# c2020_schematic.net
KiCad netlist of a schematic drawn in Altium Designer
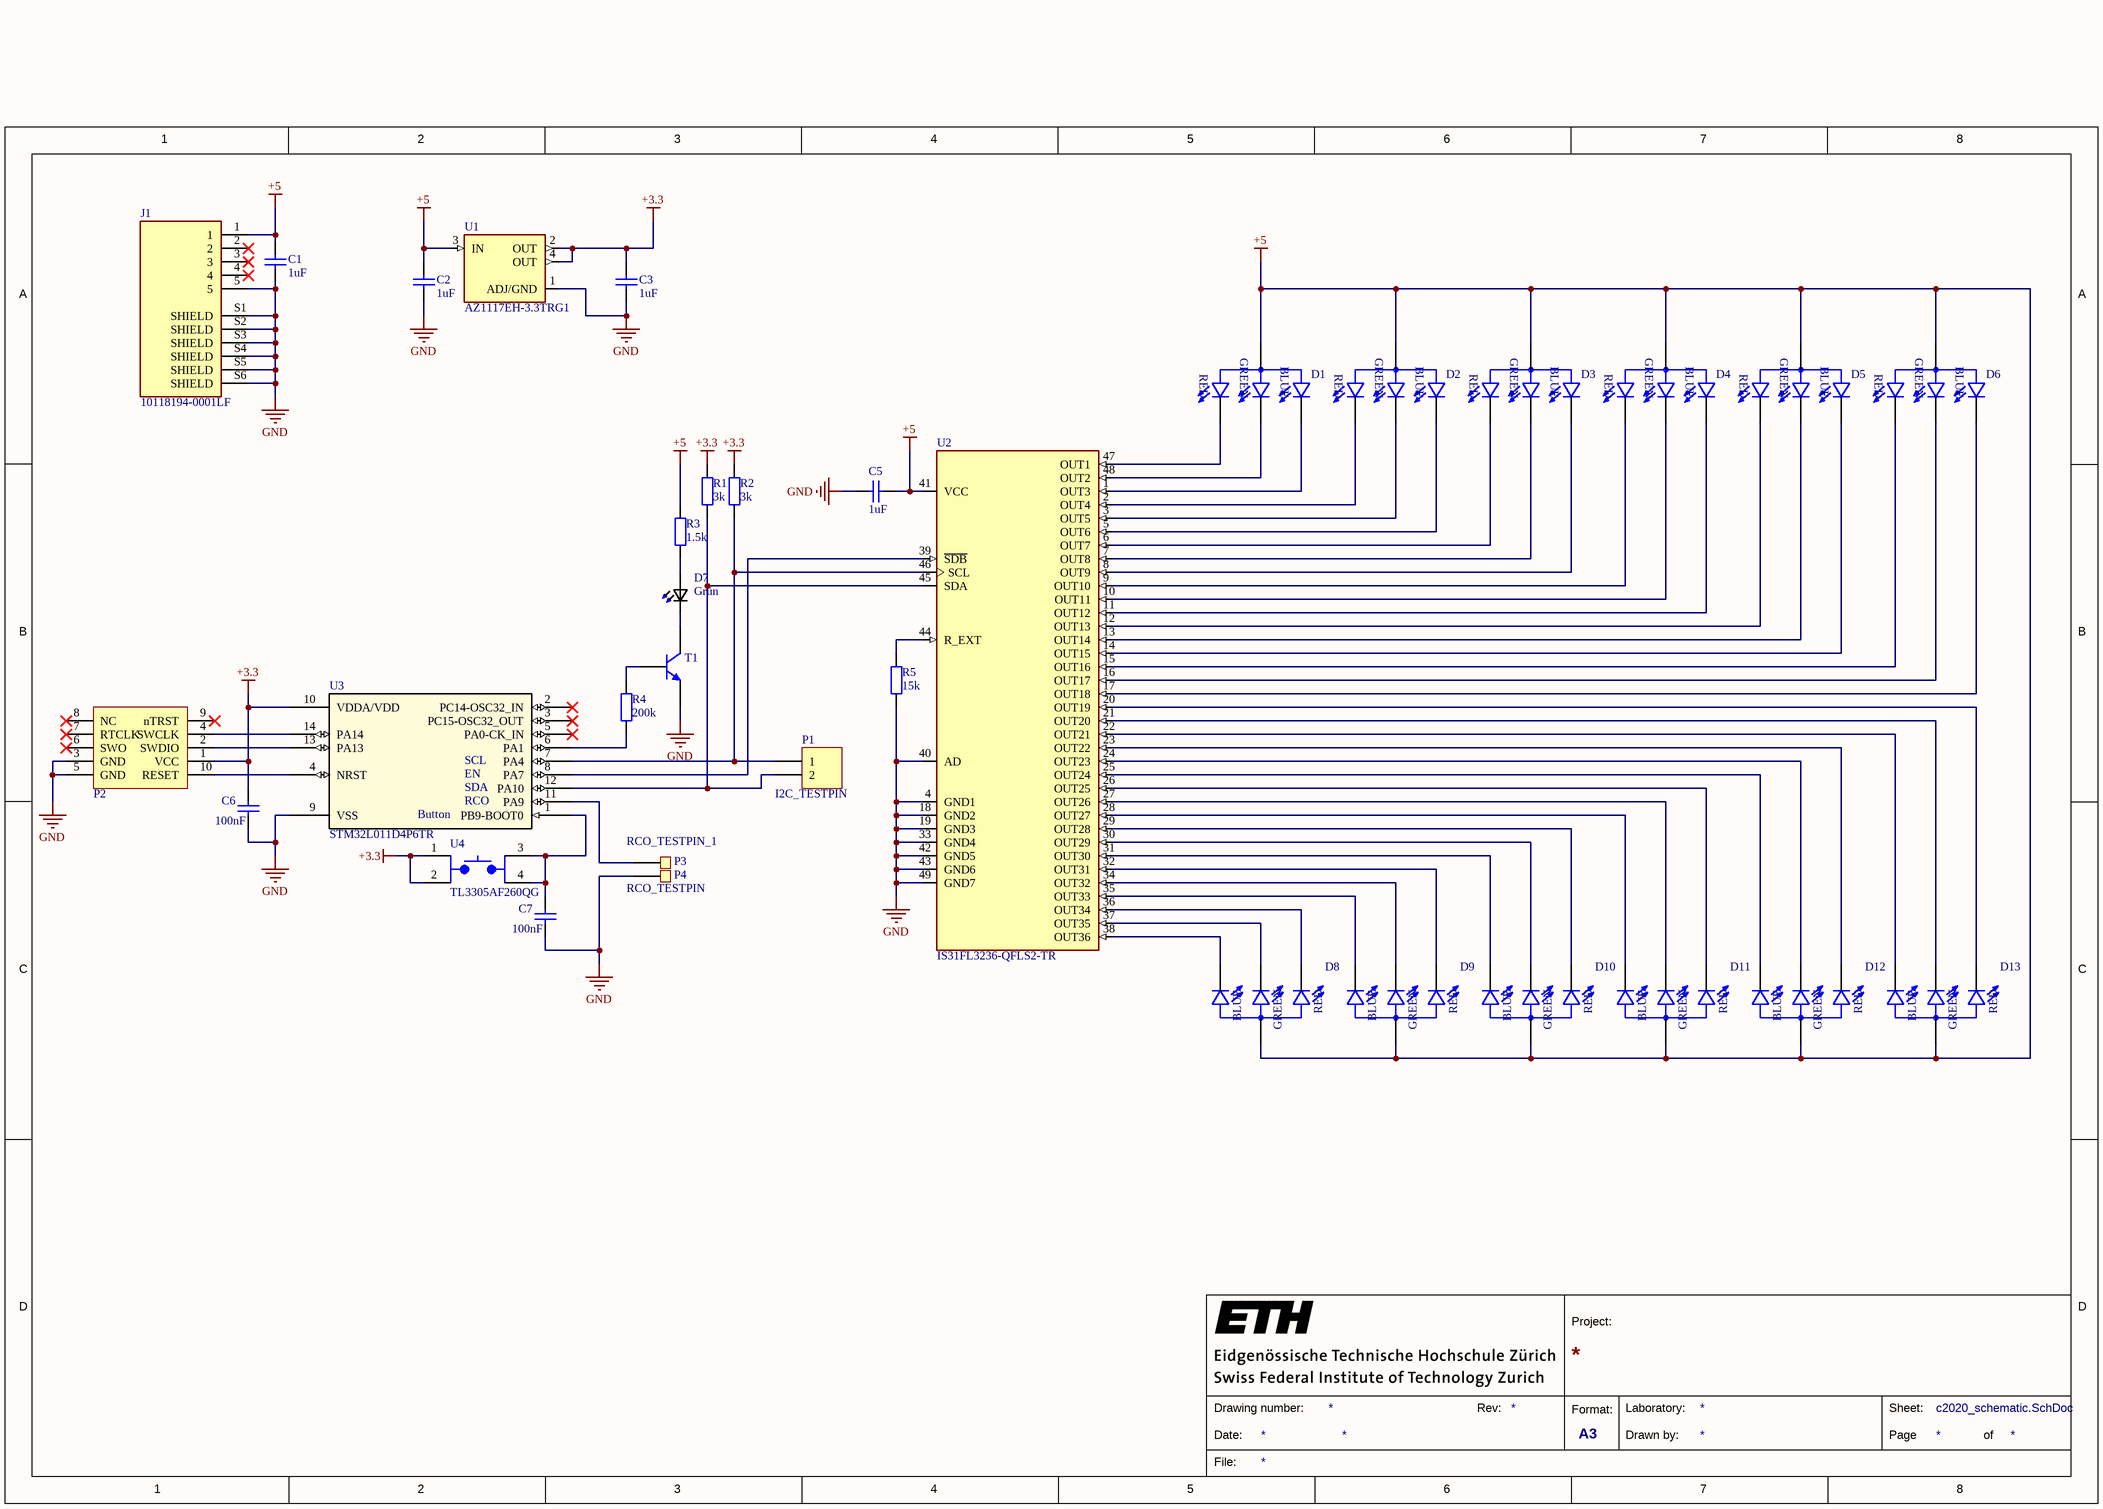
[diagram p0: c2020_schematic.SchDoc]

(export (version "E")
  (design (tool "Eeschema 10.0.6"))
  (components
    (comp (ref "C1")
      (value "1uF")
      (footprint "CAP_0603i_1608m -N")
      (description "capacitor")
      (libsource (lib "IDSC std generic parts") (part "Cap"))
    )
    (comp (ref "C2")
      (value "1uF")
      (footprint "CAP_0603i_1608m -N")
      (description "capacitor")
      (libsource (lib "IDSC std generic parts") (part "Cap"))
    )
    (comp (ref "C3")
      (value "1uF")
      (footprint "CAP_0603i_1608m -N")
      (description "capacitor")
      (libsource (lib "IDSC std generic parts") (part "Cap"))
    )
    (comp (ref "C5")
      (value "1uF")
      (footprint "CAP_0603i_1608m -N")
      (description "capacitor")
      (libsource (lib "IDSC std generic parts") (part "Cap"))
    )
    (comp (ref "C6")
      (value "100nF")
      (footprint "CAP_0402i_1005m -N")
      (description "capacitor")
      (libsource (lib "IDSC std generic parts") (part "Cap"))
    )
    (comp (ref "C7")
      (value "100nF")
      (footprint "CAP_0402i_1005m -N")
      (description "capacitor")
      (libsource (lib "IDSC std generic parts") (part "Cap"))
    )
    (comp (ref "D1")
      (value "156120M173000")
      (footprint "LED_156120M173000")
      (fields (field (name "MF") "Wurth Electronics"))
      (libsource (lib "lib_c2020") (part "156120M173000"))
    )
    (comp (ref "D2")
      (value "156120M173000")
      (footprint "LED_156120M173000")
      (fields (field (name "MF") "Wurth Electronics"))
      (libsource (lib "lib_c2020") (part "156120M173000"))
    )
    (comp (ref "D3")
      (value "156120M173000")
      (footprint "LED_156120M173000")
      (fields (field (name "MF") "Wurth Electronics"))
      (libsource (lib "lib_c2020") (part "156120M173000"))
    )
    (comp (ref "D4")
      (value "156120M173000")
      (footprint "LED_156120M173000")
      (fields (field (name "MF") "Wurth Electronics"))
      (libsource (lib "lib_c2020") (part "156120M173000"))
    )
    (comp (ref "D5")
      (value "156120M173000")
      (footprint "LED_156120M173000")
      (fields (field (name "MF") "Wurth Electronics"))
      (libsource (lib "lib_c2020") (part "156120M173000"))
    )
    (comp (ref "D6")
      (value "156120M173000")
      (footprint "LED_156120M173000")
      (fields (field (name "MF") "Wurth Electronics"))
      (libsource (lib "lib_c2020") (part "156120M173000"))
    )
    (comp (ref "D7")
      (value "Grün")
      (footprint "*0603")
      (description "LED; SMD; 0603; gr黱; 35mcd; 1.6x0.8x0.55mm; 130掳; 2梅2.V; 20mA")
      (fields (field (name "MP") "LTST-C191KGKT") (field (name "DIGI-KEY_PART_NUMBER") "160-1446-1-ND"))
      (libsource (lib "Funk") (part "LTST-C191KGKT"))
    )
    (comp (ref "D8")
      (value "156120M173000")
      (footprint "LED_156120M173000")
      (fields (field (name "MF") "Wurth Electronics"))
      (libsource (lib "lib_c2020") (part "156120M173000"))
    )
    (comp (ref "D9")
      (value "156120M173000")
      (footprint "LED_156120M173000")
      (fields (field (name "MF") "Wurth Electronics"))
      (libsource (lib "lib_c2020") (part "156120M173000"))
    )
    (comp (ref "D10")
      (value "156120M173000")
      (footprint "LED_156120M173000")
      (fields (field (name "MF") "Wurth Electronics"))
      (libsource (lib "lib_c2020") (part "156120M173000"))
    )
    (comp (ref "D11")
      (value "156120M173000")
      (footprint "LED_156120M173000")
      (fields (field (name "MF") "Wurth Electronics"))
      (libsource (lib "lib_c2020") (part "156120M173000"))
    )
    (comp (ref "D12")
      (value "156120M173000")
      (footprint "LED_156120M173000")
      (fields (field (name "MF") "Wurth Electronics"))
      (libsource (lib "lib_c2020") (part "156120M173000"))
    )
    (comp (ref "D13")
      (value "156120M173000")
      (footprint "LED_156120M173000")
      (fields (field (name "MF") "Wurth Electronics"))
      (libsource (lib "lib_c2020") (part "156120M173000"))
    )
    (comp (ref "J1")
      (value "10118194-0001LF")
      (footprint "AMPHENOL_10118194-0001LF")
      (description "USB - micro B USB 2.0 Receptacle Connector 5 Position Surface Mount, Right Angle; Through Hole")
      (fields (field (name "MF") "Amphenol ICC"))
      (libsource (lib "lib_c2020") (part "10118194-0001LF"))
    )
    (comp (ref "P1")
      (value "I2C_TESTPIN")
      (footprint "HDR1X2")
      (description "Header, 2-Pin")
      (libsource (lib "IDSC std connectors") (part "Header 2"))
    )
    (comp (ref "P2")
      (value "Tag-Connect TC2050-IDC-NL-No pin assigned")
      (footprint "TAG-CONNECT TC2050-IDC-NL 10-Pin")
      (description "10-pin pogo pin programing port")
      (libsource (lib "IDSC std connectors") (part "Tag-Connect TC2050-IDC-NL-No pin assigned"))
    )
    (comp (ref "P3")
      (value "RCO_TESTPIN_1")
      (footprint "Pad_0603")
      (description "Single Pad or Testpoint")
      (libsource (lib "IDSC std connectors") (part "Pad"))
    )
    (comp (ref "P4")
      (value "RCO_TESTPIN")
      (footprint "Pad_0603")
      (description "Single Pad or Testpoint")
      (libsource (lib "IDSC std connectors") (part "Pad"))
    )
    (comp (ref "R1")
      (value "3k")
      (footprint "RES_0402i_1005m -N")
      (description "Resistor")
      (libsource (lib "IDSC std generic parts") (part "Res"))
    )
    (comp (ref "R2")
      (value "3k")
      (footprint "RES_0402i_1005m -N")
      (description "Resistor")
      (libsource (lib "IDSC std generic parts") (part "Res"))
    )
    (comp (ref "R3")
      (value "1.5k")
      (footprint "RES_0402i_1005m -N")
      (description "Resistor")
      (libsource (lib "IDSC std generic parts") (part "Res"))
    )
    (comp (ref "R4")
      (value "200k")
      (footprint "RES_0402i_1005m -N")
      (description "Resistor")
      (libsource (lib "IDSC std generic parts") (part "Res"))
    )
    (comp (ref "R5")
      (value "15k")
      (footprint "RES_0402i_1005m -N")
      (description "Resistor")
      (libsource (lib "IDSC std generic parts") (part "Res"))
    )
    (comp (ref "T1")
      (value "BJT NPN")
      (footprint "SOT23-N")
      (description "NPN Bipolar Transistor")
      (libsource (lib "IDSC std generic parts") (part "BJT NPN"))
    )
    (comp (ref "U1")
      (value "AZ1117EH-3.3TRG1")
      (footprint "SOT230P700X180-4N")
      (description "Linear Voltage Regulator IC 1 Output 1A SOT-223")
      (fields (field (name "MF") "Diodes Inc."))
      (libsource (lib "lib_c2020") (part "AZ1117EH-3.3TRG1"))
    )
    (comp (ref "U2")
      (value "IS31FL3236-QFLS2-TR")
      (footprint "QFP50P900X900X160-48N")
      (description "LED Driver IC 36 Output Linear IÂ²C Dimming 38mA 44-QFN (5x5)")
      (fields (field (name "MF") "ISSI, Integrated") (field (name "DIGI-KEY_PART_NUMBER") "706-1434-1-ND"))
      (libsource (lib "lib_c2020") (part "IS31FL3236-QFLS2-TR"))
    )
    (comp (ref "U3")
      (value "STM32L011D4P6TR")
      (footprint "TSSOP14")
      (description "No Description Available")
      (fields (field (name "COPYRIGHT") "Copyright (C) 2018 Accelerated Designs. All rights reserved"))
      (libsource (lib "lib_c2020") (part "STM32L011D4P6TR"))
    )
    (comp (ref "U4")
      (value "TL3305AF260QG")
      (footprint "SW_TL3305AF260QG")
      (description "Tactile Switch SPST-NO Top Actuated Surface Mount")
      (fields (field (name "MF") "E-Switch"))
      (libsource (lib "lib_c2020") (part "TL3305AF260QG"))
    )
  )
  (nets
    (net (code "1") (name "+3.3") (class "Default")
      (node (ref "C3") (pin "2") (pinfunction "2_2") (pintype "passive"))
      (node (ref "C6") (pin "2") (pinfunction "2_2") (pintype "passive"))
      (node (ref "P2") (pin "1") (pinfunction "VCC_1") (pintype "passive"))
      (node (ref "R1") (pin "2") (pinfunction "2_2") (pintype "passive"))
      (node (ref "R2") (pin "2") (pinfunction "2_2") (pintype "passive"))
      (node (ref "U1") (pin "2") (pinfunction "OUT_2") (pintype "output"))
      (node (ref "U1") (pin "4") (pinfunction "OUT_4") (pintype "output"))
      (node (ref "U3") (pin "10") (pinfunction "VDDA/VDD_10") (pintype "power_in"))
      (node (ref "U4") (pin "1") (pinfunction "1_1") (pintype "passive"))
      (node (ref "U4") (pin "2") (pinfunction "2_2") (pintype "passive"))
    )
    (net (code "2") (name "+5") (class "Default")
      (node (ref "C1") (pin "2") (pinfunction "2_2") (pintype "passive"))
      (node (ref "C2") (pin "2") (pinfunction "2_2") (pintype "passive"))
      (node (ref "C5") (pin "2") (pinfunction "2_2") (pintype "passive"))
      (node (ref "D1") (pin "1") (pinfunction "A_1") (pintype "passive"))
      (node (ref "D10") (pin "1") (pinfunction "A_1") (pintype "passive"))
      (node (ref "D11") (pin "1") (pinfunction "A_1") (pintype "passive"))
      (node (ref "D12") (pin "1") (pinfunction "A_1") (pintype "passive"))
      (node (ref "D13") (pin "1") (pinfunction "A_1") (pintype "passive"))
      (node (ref "D2") (pin "1") (pinfunction "A_1") (pintype "passive"))
      (node (ref "D3") (pin "1") (pinfunction "A_1") (pintype "passive"))
      (node (ref "D4") (pin "1") (pinfunction "A_1") (pintype "passive"))
      (node (ref "D5") (pin "1") (pinfunction "A_1") (pintype "passive"))
      (node (ref "D6") (pin "1") (pinfunction "A_1") (pintype "passive"))
      (node (ref "D8") (pin "1") (pinfunction "A_1") (pintype "passive"))
      (node (ref "D9") (pin "1") (pinfunction "A_1") (pintype "passive"))
      (node (ref "J1") (pin "1") (pinfunction "1_1") (pintype "passive"))
      (node (ref "R3") (pin "2") (pinfunction "2_2") (pintype "passive"))
      (node (ref "U1") (pin "3") (pinfunction "IN_3") (pintype "input"))
      (node (ref "U2") (pin "41") (pinfunction "VCC_41") (pintype "power_in"))
    )
    (net (code "3") (name "GND") (class "Default")
      (node (ref "C1") (pin "1") (pinfunction "1_1") (pintype "passive"))
      (node (ref "C2") (pin "1") (pinfunction "1_1") (pintype "passive"))
      (node (ref "C3") (pin "1") (pinfunction "1_1") (pintype "passive"))
      (node (ref "C5") (pin "1") (pinfunction "1_1") (pintype "passive"))
      (node (ref "C6") (pin "1") (pinfunction "1_1") (pintype "passive"))
      (node (ref "C7") (pin "1") (pinfunction "1_1") (pintype "passive"))
      (node (ref "J1") (pin "5") (pinfunction "5_5") (pintype "passive"))
      (node (ref "J1") (pin "S1") (pinfunction "SHIELD_S1") (pintype "passive"))
      (node (ref "J1") (pin "S2") (pinfunction "SHIELD_S2") (pintype "passive"))
      (node (ref "J1") (pin "S3") (pinfunction "SHIELD_S3") (pintype "passive"))
      (node (ref "J1") (pin "S4") (pinfunction "SHIELD_S4") (pintype "passive"))
      (node (ref "J1") (pin "S5") (pinfunction "SHIELD_S5") (pintype "passive"))
      (node (ref "J1") (pin "S6") (pinfunction "SHIELD_S6") (pintype "passive"))
      (node (ref "P2") (pin "3") (pinfunction "GND_3") (pintype "passive"))
      (node (ref "P2") (pin "5") (pinfunction "GND_5") (pintype "passive"))
      (node (ref "P4") (pin "1") (pinfunction "1_1") (pintype "passive"))
      (node (ref "R5") (pin "1") (pinfunction "1_1") (pintype "passive"))
      (node (ref "T1") (pin "2") (pinfunction "E_2") (pintype "passive"))
      (node (ref "U1") (pin "1") (pinfunction "ADJ/GND_1") (pintype "power_in"))
      (node (ref "U2") (pin "18") (pinfunction "GND2_18") (pintype "power_in"))
      (node (ref "U2") (pin "19") (pinfunction "GND3_19") (pintype "power_in"))
      (node (ref "U2") (pin "33") (pinfunction "GND4_33") (pintype "power_in"))
      (node (ref "U2") (pin "4") (pinfunction "GND1_4") (pintype "power_in"))
      (node (ref "U2") (pin "40") (pinfunction "AD_40") (pintype "bidirectional"))
      (node (ref "U2") (pin "42") (pinfunction "GND5_42") (pintype "power_in"))
      (node (ref "U2") (pin "43") (pinfunction "GND6_43") (pintype "power_in"))
      (node (ref "U2") (pin "49") (pinfunction "GND7_49") (pintype "power_in"))
      (node (ref "U3") (pin "9") (pinfunction "VSS_9") (pintype "power_in"))
    )
    (net (code "4") (name "Net-(D1-B_C)") (class "Default")
      (node (ref "D1") (pin "2") (pinfunction "B_C_2") (pintype "passive"))
      (node (ref "U2") (pin "1") (pinfunction "OUT3_1") (pintype "input"))
    )
    (net (code "5") (name "Net-(D1-G_C)") (class "Default")
      (node (ref "D1") (pin "4") (pinfunction "G_C_4") (pintype "passive"))
      (node (ref "U2") (pin "48") (pinfunction "OUT2_48") (pintype "input"))
    )
    (net (code "6") (name "Net-(D1-R_C)") (class "Default")
      (node (ref "D1") (pin "3") (pinfunction "R_C_3") (pintype "passive"))
      (node (ref "U2") (pin "47") (pinfunction "OUT1_47") (pintype "input"))
    )
    (net (code "7") (name "Net-(D2-B_C)") (class "Default")
      (node (ref "D2") (pin "2") (pinfunction "B_C_2") (pintype "passive"))
      (node (ref "U2") (pin "5") (pinfunction "OUT6_5") (pintype "input"))
    )
    (net (code "8") (name "Net-(D2-G_C)") (class "Default")
      (node (ref "D2") (pin "4") (pinfunction "G_C_4") (pintype "passive"))
      (node (ref "U2") (pin "3") (pinfunction "OUT5_3") (pintype "input"))
    )
    (net (code "9") (name "Net-(D2-R_C)") (class "Default")
      (node (ref "D2") (pin "3") (pinfunction "R_C_3") (pintype "passive"))
      (node (ref "U2") (pin "2") (pinfunction "OUT4_2") (pintype "input"))
    )
    (net (code "10") (name "Net-(D3-B_C)") (class "Default")
      (node (ref "D3") (pin "2") (pinfunction "B_C_2") (pintype "passive"))
      (node (ref "U2") (pin "8") (pinfunction "OUT9_8") (pintype "input"))
    )
    (net (code "11") (name "Net-(D3-G_C)") (class "Default")
      (node (ref "D3") (pin "4") (pinfunction "G_C_4") (pintype "passive"))
      (node (ref "U2") (pin "7") (pinfunction "OUT8_7") (pintype "input"))
    )
    (net (code "12") (name "Net-(D3-R_C)") (class "Default")
      (node (ref "D3") (pin "3") (pinfunction "R_C_3") (pintype "passive"))
      (node (ref "U2") (pin "6") (pinfunction "OUT7_6") (pintype "input"))
    )
    (net (code "13") (name "Net-(D4-B_C)") (class "Default")
      (node (ref "D4") (pin "2") (pinfunction "B_C_2") (pintype "passive"))
      (node (ref "U2") (pin "11") (pinfunction "OUT12_11") (pintype "input"))
    )
    (net (code "14") (name "Net-(D4-G_C)") (class "Default")
      (node (ref "D4") (pin "4") (pinfunction "G_C_4") (pintype "passive"))
      (node (ref "U2") (pin "10") (pinfunction "OUT11_10") (pintype "input"))
    )
    (net (code "15") (name "Net-(D4-R_C)") (class "Default")
      (node (ref "D4") (pin "3") (pinfunction "R_C_3") (pintype "passive"))
      (node (ref "U2") (pin "9") (pinfunction "OUT10_9") (pintype "input"))
    )
    (net (code "16") (name "Net-(D5-B_C)") (class "Default")
      (node (ref "D5") (pin "2") (pinfunction "B_C_2") (pintype "passive"))
      (node (ref "U2") (pin "14") (pinfunction "OUT15_14") (pintype "input"))
    )
    (net (code "17") (name "Net-(D5-G_C)") (class "Default")
      (node (ref "D5") (pin "4") (pinfunction "G_C_4") (pintype "passive"))
      (node (ref "U2") (pin "13") (pinfunction "OUT14_13") (pintype "input"))
    )
    (net (code "18") (name "Net-(D5-R_C)") (class "Default")
      (node (ref "D5") (pin "3") (pinfunction "R_C_3") (pintype "passive"))
      (node (ref "U2") (pin "12") (pinfunction "OUT13_12") (pintype "input"))
    )
    (net (code "19") (name "Net-(D6-B_C)") (class "Default")
      (node (ref "D6") (pin "2") (pinfunction "B_C_2") (pintype "passive"))
      (node (ref "U2") (pin "17") (pinfunction "OUT18_17") (pintype "input"))
    )
    (net (code "20") (name "Net-(D6-G_C)") (class "Default")
      (node (ref "D6") (pin "4") (pinfunction "G_C_4") (pintype "passive"))
      (node (ref "U2") (pin "16") (pinfunction "OUT17_16") (pintype "input"))
    )
    (net (code "21") (name "Net-(D6-R_C)") (class "Default")
      (node (ref "D6") (pin "3") (pinfunction "R_C_3") (pintype "passive"))
      (node (ref "U2") (pin "15") (pinfunction "OUT16_15") (pintype "input"))
    )
    (net (code "22") (name "Net-(D7-A2)") (class "Default")
      (node (ref "D7") (pin "2") (pinfunction "A2_2") (pintype "passive"))
      (node (ref "R3") (pin "1") (pinfunction "1_1") (pintype "passive"))
    )
    (net (code "23") (name "Net-(D7-K2)") (class "Default")
      (node (ref "D7") (pin "1") (pinfunction "K2_1") (pintype "passive"))
      (node (ref "T1") (pin "3") (pinfunction "C_3") (pintype "passive"))
    )
    (net (code "24") (name "Net-(D8-B_C)") (class "Default")
      (node (ref "D8") (pin "2") (pinfunction "B_C_2") (pintype "passive"))
      (node (ref "U2") (pin "38") (pinfunction "OUT36_38") (pintype "input"))
    )
    (net (code "25") (name "Net-(D8-G_C)") (class "Default")
      (node (ref "D8") (pin "4") (pinfunction "G_C_4") (pintype "passive"))
      (node (ref "U2") (pin "37") (pinfunction "OUT35_37") (pintype "input"))
    )
    (net (code "26") (name "Net-(D8-R_C)") (class "Default")
      (node (ref "D8") (pin "3") (pinfunction "R_C_3") (pintype "passive"))
      (node (ref "U2") (pin "36") (pinfunction "OUT34_36") (pintype "input"))
    )
    (net (code "27") (name "Net-(D9-B_C)") (class "Default")
      (node (ref "D9") (pin "2") (pinfunction "B_C_2") (pintype "passive"))
      (node (ref "U2") (pin "35") (pinfunction "OUT33_35") (pintype "input"))
    )
    (net (code "28") (name "Net-(D9-G_C)") (class "Default")
      (node (ref "D9") (pin "4") (pinfunction "G_C_4") (pintype "passive"))
      (node (ref "U2") (pin "34") (pinfunction "OUT32_34") (pintype "input"))
    )
    (net (code "29") (name "Net-(D9-R_C)") (class "Default")
      (node (ref "D9") (pin "3") (pinfunction "R_C_3") (pintype "passive"))
      (node (ref "U2") (pin "32") (pinfunction "OUT31_32") (pintype "input"))
    )
    (net (code "30") (name "Net-(D10-B_C)") (class "Default")
      (node (ref "D10") (pin "2") (pinfunction "B_C_2") (pintype "passive"))
      (node (ref "U2") (pin "31") (pinfunction "OUT30_31") (pintype "input"))
    )
    (net (code "31") (name "Net-(D10-G_C)") (class "Default")
      (node (ref "D10") (pin "4") (pinfunction "G_C_4") (pintype "passive"))
      (node (ref "U2") (pin "30") (pinfunction "OUT29_30") (pintype "input"))
    )
    (net (code "32") (name "Net-(D10-R_C)") (class "Default")
      (node (ref "D10") (pin "3") (pinfunction "R_C_3") (pintype "passive"))
      (node (ref "U2") (pin "29") (pinfunction "OUT28_29") (pintype "input"))
    )
    (net (code "33") (name "Net-(D11-B_C)") (class "Default")
      (node (ref "D11") (pin "2") (pinfunction "B_C_2") (pintype "passive"))
      (node (ref "U2") (pin "28") (pinfunction "OUT27_28") (pintype "input"))
    )
    (net (code "34") (name "Net-(D11-G_C)") (class "Default")
      (node (ref "D11") (pin "4") (pinfunction "G_C_4") (pintype "passive"))
      (node (ref "U2") (pin "27") (pinfunction "OUT26_27") (pintype "input"))
    )
    (net (code "35") (name "Net-(D11-R_C)") (class "Default")
      (node (ref "D11") (pin "3") (pinfunction "R_C_3") (pintype "passive"))
      (node (ref "U2") (pin "26") (pinfunction "OUT25_26") (pintype "input"))
    )
    (net (code "36") (name "Net-(D12-B_C)") (class "Default")
      (node (ref "D12") (pin "2") (pinfunction "B_C_2") (pintype "passive"))
      (node (ref "U2") (pin "25") (pinfunction "OUT24_25") (pintype "input"))
    )
    (net (code "37") (name "Net-(D12-G_C)") (class "Default")
      (node (ref "D12") (pin "4") (pinfunction "G_C_4") (pintype "passive"))
      (node (ref "U2") (pin "24") (pinfunction "OUT23_24") (pintype "input"))
    )
    (net (code "38") (name "Net-(D12-R_C)") (class "Default")
      (node (ref "D12") (pin "3") (pinfunction "R_C_3") (pintype "passive"))
      (node (ref "U2") (pin "23") (pinfunction "OUT22_23") (pintype "input"))
    )
    (net (code "39") (name "Net-(D13-B_C)") (class "Default")
      (node (ref "D13") (pin "2") (pinfunction "B_C_2") (pintype "passive"))
      (node (ref "U2") (pin "22") (pinfunction "OUT21_22") (pintype "input"))
    )
    (net (code "40") (name "Net-(D13-G_C)") (class "Default")
      (node (ref "D13") (pin "4") (pinfunction "G_C_4") (pintype "passive"))
      (node (ref "U2") (pin "21") (pinfunction "OUT20_21") (pintype "input"))
    )
    (net (code "41") (name "Net-(D13-R_C)") (class "Default")
      (node (ref "D13") (pin "3") (pinfunction "R_C_3") (pintype "passive"))
      (node (ref "U2") (pin "20") (pinfunction "OUT19_20") (pintype "input"))
    )
    (net (code "42") (name "Net-(P2-RESET)") (class "Default")
      (node (ref "P2") (pin "10") (pinfunction "RESET_10") (pintype "passive"))
      (node (ref "U3") (pin "4") (pinfunction "NRST_4") (pintype "bidirectional"))
    )
    (net (code "43") (name "Net-(P2-SWCLK)") (class "Default")
      (node (ref "P2") (pin "4") (pinfunction "SWCLK_4") (pintype "passive"))
      (node (ref "U3") (pin "14") (pinfunction "PA14_14") (pintype "bidirectional"))
    )
    (net (code "44") (name "Net-(P2-SWDIO)") (class "Default")
      (node (ref "P2") (pin "2") (pinfunction "SWDIO_2") (pintype "passive"))
      (node (ref "U3") (pin "13") (pinfunction "PA13_13") (pintype "bidirectional"))
    )
    (net (code "45") (name "Net-(T1-B)") (class "Default")
      (node (ref "R4") (pin "2") (pinfunction "2_2") (pintype "passive"))
      (node (ref "T1") (pin "1") (pinfunction "B_1") (pintype "passive"))
    )
    (net (code "46") (name "Net-(U2-R_EXT)") (class "Default")
      (node (ref "R5") (pin "2") (pinfunction "2_2") (pintype "passive"))
      (node (ref "U2") (pin "44") (pinfunction "R_EXT_44") (pintype "input"))
    )
    (net (code "47") (name "Net-(U2-SCL)") (class "Default")
      (node (ref "P1") (pin "1") (pinfunction "1_1") (pintype "passive"))
      (node (ref "R2") (pin "1") (pinfunction "1_1") (pintype "passive"))
      (node (ref "U2") (pin "46") (pinfunction "SCL_46") (pintype "bidirectional"))
      (node (ref "U3") (pin "7") (pinfunction "PA4_7") (pintype "bidirectional"))
    )
    (net (code "48") (name "Net-(U2-SDA)") (class "Default")
      (node (ref "P1") (pin "2") (pinfunction "2_2") (pintype "passive"))
      (node (ref "R1") (pin "1") (pinfunction "1_1") (pintype "passive"))
      (node (ref "U2") (pin "45") (pinfunction "SDA_45") (pintype "bidirectional"))
      (node (ref "U3") (pin "12") (pinfunction "PA10_12") (pintype "bidirectional"))
    )
    (net (code "49") (name "Net-(U2-~{SDB})") (class "Default")
      (node (ref "U2") (pin "39") (pinfunction "~{SDB}_39") (pintype "input"))
      (node (ref "U3") (pin "8") (pinfunction "PA7_8") (pintype "bidirectional"))
    )
    (net (code "50") (name "Net-(U3-PA1)") (class "Default")
      (node (ref "R4") (pin "1") (pinfunction "1_1") (pintype "passive"))
      (node (ref "U3") (pin "6") (pinfunction "PA1_6") (pintype "bidirectional"))
    )
    (net (code "51") (name "Net-(U3-PA9)") (class "Default")
      (node (ref "P3") (pin "1") (pinfunction "1_1") (pintype "passive"))
      (node (ref "U3") (pin "11") (pinfunction "PA9_11") (pintype "bidirectional"))
    )
    (net (code "52") (name "Net-(U3-PB9-BOOT0)") (class "Default")
      (node (ref "C7") (pin "2") (pinfunction "2_2") (pintype "passive"))
      (node (ref "U3") (pin "1") (pinfunction "PB9-BOOT0_1") (pintype "input"))
      (node (ref "U4") (pin "3") (pinfunction "3_3") (pintype "passive"))
      (node (ref "U4") (pin "4") (pinfunction "4_4") (pintype "passive"))
    )
    (net (code "53") (name "unconnected-(J1-Pad2)") (class "Default")
      (node (ref "J1") (pin "2") (pinfunction "2_2") (pintype "passive+no_connect"))
    )
    (net (code "54") (name "unconnected-(J1-Pad3)") (class "Default")
      (node (ref "J1") (pin "3") (pinfunction "3_3") (pintype "passive+no_connect"))
    )
    (net (code "55") (name "unconnected-(J1-Pad4)") (class "Default")
      (node (ref "J1") (pin "4") (pinfunction "4_4") (pintype "passive+no_connect"))
    )
    (net (code "56") (name "unconnected-(P2-NC-Pad8)") (class "Default")
      (node (ref "P2") (pin "8") (pinfunction "NC_8") (pintype "passive+no_connect"))
    )
    (net (code "57") (name "unconnected-(P2-RTCLK-Pad7)") (class "Default")
      (node (ref "P2") (pin "7") (pinfunction "RTCLK_7") (pintype "passive+no_connect"))
    )
    (net (code "58") (name "unconnected-(P2-SWO-Pad6)") (class "Default")
      (node (ref "P2") (pin "6") (pinfunction "SWO_6") (pintype "passive+no_connect"))
    )
    (net (code "59") (name "unconnected-(P2-nTRST-Pad9)") (class "Default")
      (node (ref "P2") (pin "9") (pinfunction "nTRST_9") (pintype "passive+no_connect"))
    )
    (net (code "60") (name "unconnected-(U3-PA0-CK_IN-Pad5)") (class "Default")
      (node (ref "U3") (pin "5") (pinfunction "PA0-CK_IN_5") (pintype "bidirectional+no_connect"))
    )
    (net (code "61") (name "unconnected-(U3-PC14-OSC32_IN-Pad2)") (class "Default")
      (node (ref "U3") (pin "2") (pinfunction "PC14-OSC32_IN_2") (pintype "bidirectional+no_connect"))
    )
    (net (code "62") (name "unconnected-(U3-PC15-OSC32_OUT-Pad3)") (class "Default")
      (node (ref "U3") (pin "3") (pinfunction "PC15-OSC32_OUT_3") (pintype "bidirectional+no_connect"))
    )
  )
)
